# PS_TPS54340_Voltage_CurrentRev2.net
KiCad netlist of a schematic drawn in EAGLE
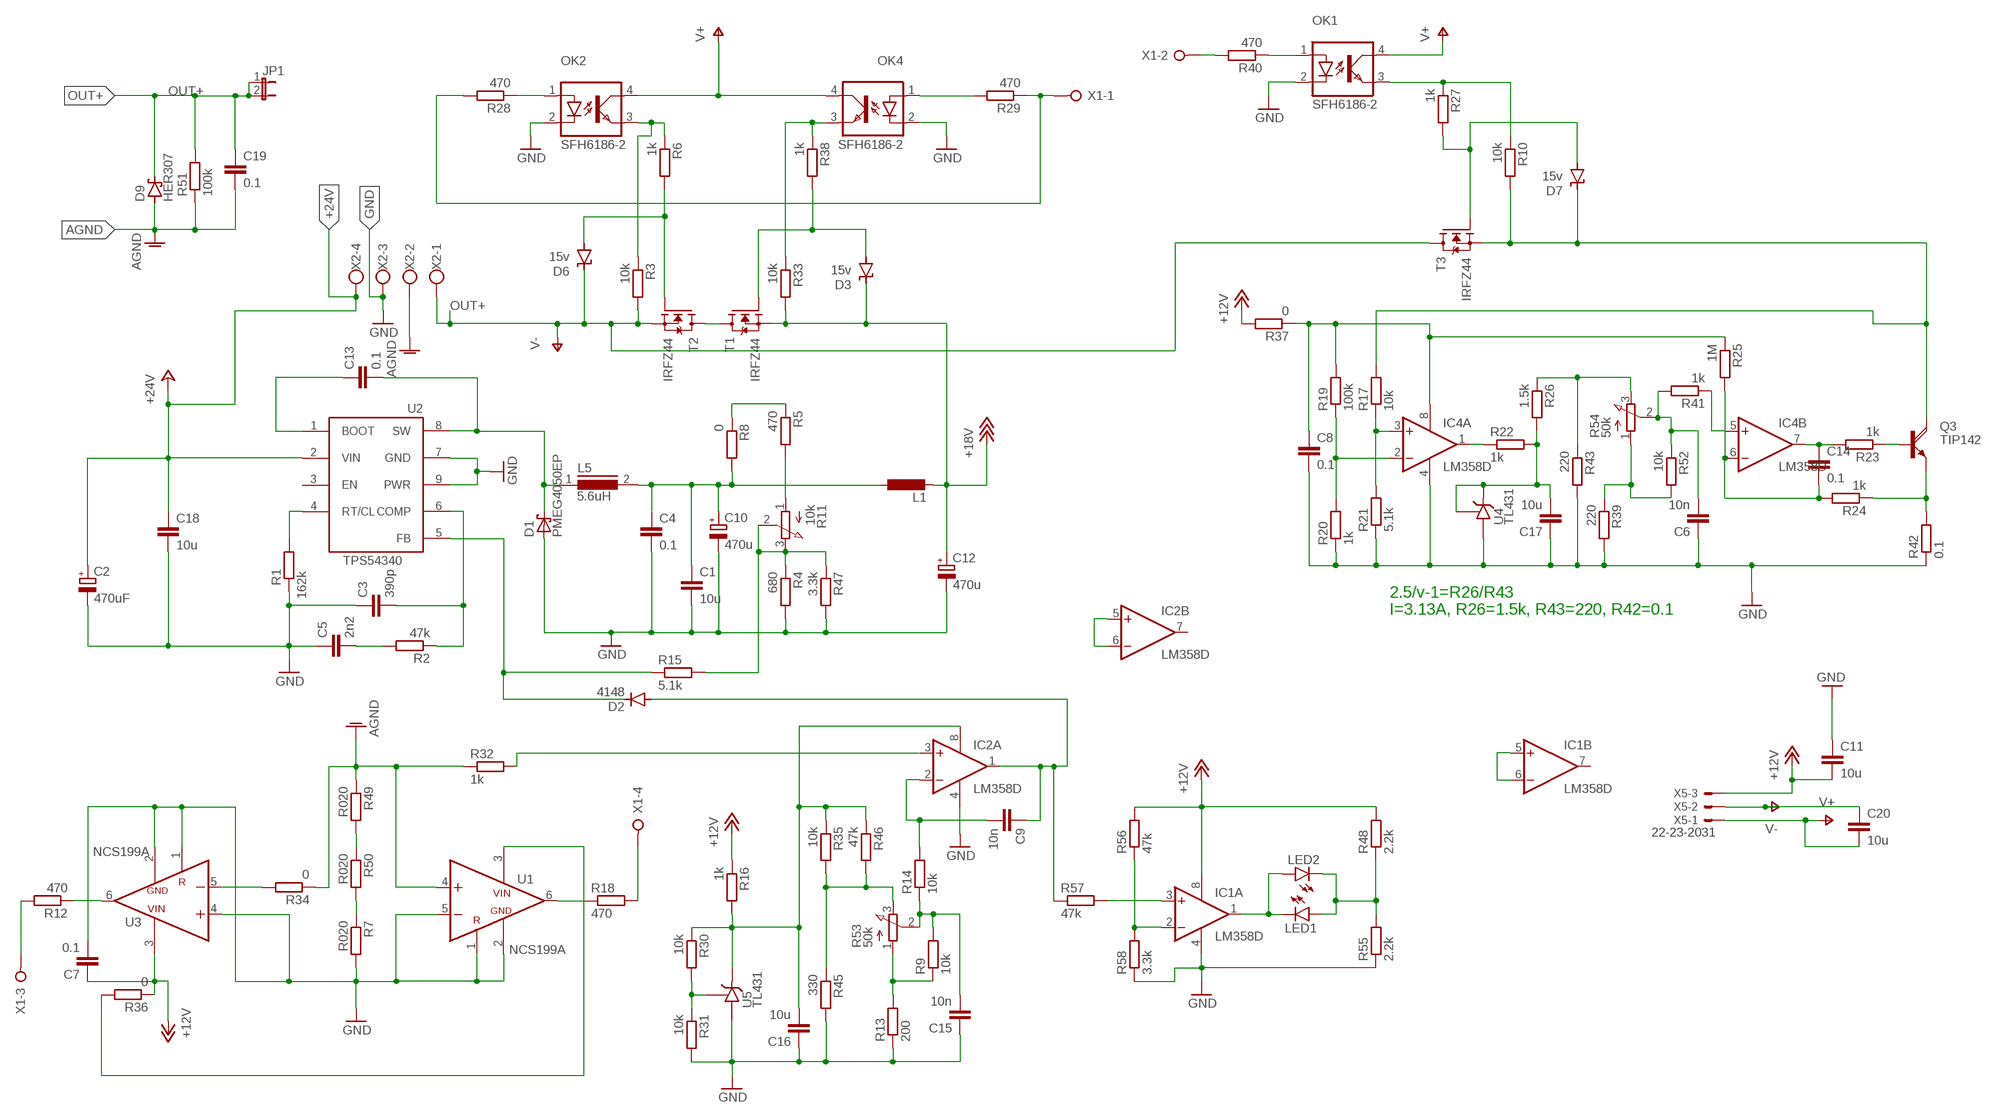
[diagram p0: schematic, sheet 1]

(export (version "E")
  (design (tool "Eeschema 10.0.6"))
  (components
    (comp (ref "C1")
      (value "10u")
      (footprint "eagle-import:C1210")
      (libsource (lib "eagle-import") (part "rcl_334_C-EUC1210"))
    )
    (comp (ref "C2")
      (value "470uF")
      (footprint "eagle-import:E5-10,5")
      (libsource (lib "eagle-import") (part "CPOL-EUE5-10.5"))
    )
    (comp (ref "C3")
      (value "390p")
      (footprint "eagle-import:C0603K")
      (libsource (lib "eagle-import") (part "rcl_334_C-EUC0603K"))
    )
    (comp (ref "C4")
      (value "0.1")
      (footprint "eagle-import:C1206")
      (libsource (lib "eagle-import") (part "C-EUC1206"))
    )
    (comp (ref "C5")
      (value "2n2")
      (footprint "eagle-import:C0603K")
      (libsource (lib "eagle-import") (part "rcl_334_C-EUC0603K"))
    )
    (comp (ref "C6")
      (value "10n")
      (footprint "eagle-import:C0603K")
      (libsource (lib "eagle-import") (part "rcl_334_C-EUC0603K"))
    )
    (comp (ref "C7")
      (value "0.1")
      (footprint "eagle-import:C0603K")
      (libsource (lib "eagle-import") (part "rcl_334_C-EUC0603K"))
    )
    (comp (ref "C8")
      (value "0.1")
      (footprint "eagle-import:C1206")
      (libsource (lib "eagle-import") (part "C-EUC1206"))
    )
    (comp (ref "C9")
      (value "10n")
      (footprint "eagle-import:C0603K")
      (libsource (lib "eagle-import") (part "rcl_334_C-EUC0603K"))
    )
    (comp (ref "C10")
      (value "470u")
      (footprint "eagle-import:E5-10,5")
      (libsource (lib "eagle-import") (part "CPOL-EUE5-10.5"))
    )
    (comp (ref "C11")
      (value "10u")
      (footprint "eagle-import:C1206")
      (libsource (lib "eagle-import") (part "C-EUC1206"))
    )
    (comp (ref "C12")
      (value "470u")
      (footprint "eagle-import:E5-10,5")
      (libsource (lib "eagle-import") (part "CPOL-EUE5-10.5"))
    )
    (comp (ref "C13")
      (value "0.1")
      (footprint "eagle-import:C102-043X133")
      (libsource (lib "eagle-import") (part "rcl_334_C-EU102-043X133"))
    )
    (comp (ref "C14")
      (value "0.1")
      (footprint "eagle-import:C1206")
      (libsource (lib "eagle-import") (part "C-EUC1206"))
    )
    (comp (ref "C15")
      (value "10n")
      (footprint "eagle-import:C0603K")
      (libsource (lib "eagle-import") (part "rcl_334_C-EUC0603K"))
    )
    (comp (ref "C16")
      (value "10u")
      (footprint "eagle-import:C0603K")
      (libsource (lib "eagle-import") (part "rcl_334_C-EUC0603K"))
    )
    (comp (ref "C17")
      (value "10u")
      (footprint "eagle-import:C0603K")
      (libsource (lib "eagle-import") (part "rcl_334_C-EUC0603K"))
    )
    (comp (ref "C18")
      (value "10u")
      (footprint "eagle-import:C1210")
      (libsource (lib "eagle-import") (part "rcl_334_C-EUC1210"))
    )
    (comp (ref "C19")
      (value "0.1")
      (footprint "eagle-import:C150-054X183")
      (libsource (lib "eagle-import") (part "rcl_334_C-EU150-054X183"))
    )
    (comp (ref "C20")
      (value "10u")
      (footprint "eagle-import:C1206")
      (libsource (lib "eagle-import") (part "C-EUC1206"))
    )
    (comp (ref "D1")
      (value "PMEG4050EP")
      (footprint "eagle-import:SOD128")
      (libsource (lib "eagle-import") (part "PMEG4050EP"))
    )
    (comp (ref "D2")
      (value "4148")
      (footprint "eagle-import:SOD80C")
      (libsource (lib "eagle-import") (part "PMLL41SOD80C"))
    )
    (comp (ref "D3")
      (value "15v")
      (footprint "eagle-import:SMBJ")
      (libsource (lib "eagle-import") (part "SUPPRESSOR-SMBJ"))
    )
    (comp (ref "D6")
      (value "15v")
      (footprint "eagle-import:SMBJ")
      (libsource (lib "eagle-import") (part "SUPPRESSOR-SMBJ"))
    )
    (comp (ref "D7")
      (value "15v")
      (footprint "eagle-import:SMBJ")
      (libsource (lib "eagle-import") (part "SUPPRESSOR-SMBJ"))
    )
    (comp (ref "D9")
      (value "HER307")
      (footprint "eagle-import:CB429-17")
      (libsource (lib "eagle-import") (part "15KEXX"))
    )
    (comp (ref "IC1")
      (value "LM358D")
      (footprint "eagle-import:SO08")
      (libsource (lib "eagle-import") (part "LM358D"))
    )
    (comp (ref "IC2")
      (value "LM358D")
      (footprint "eagle-import:SO08")
      (libsource (lib "eagle-import") (part "LM358D"))
    )
    (comp (ref "IC4")
      (value "LM358D")
      (footprint "eagle-import:SO08")
      (libsource (lib "eagle-import") (part "LM358D"))
    )
    (comp (ref "JP1")
      (value "JP1E")
      (footprint "eagle-import:JP1")
      (libsource (lib "eagle-import") (part "JP1E"))
    )
    (comp (ref "L1")
      (value "L-EU0207/5V")
      (footprint "eagle-import:0207_5V")
      (libsource (lib "eagle-import") (part "L-EU0207/5V"))
    )
    (comp (ref "L5")
      (value "5.6uH")
      (footprint "eagle-import:DR125")
      (libsource (lib "eagle-import") (part "DR125"))
    )
    (comp (ref "LED1")
      (value "LEDB152")
      (footprint "eagle-import:Q62902-B152")
      (libsource (lib "eagle-import") (part "LEDB152"))
    )
    (comp (ref "LED2")
      (value "LEDB152")
      (footprint "eagle-import:Q62902-B152")
      (libsource (lib "eagle-import") (part "LEDB152"))
    )
    (comp (ref "OK1")
      (value "SFH6186-2")
      (footprint "eagle-import:SMD4-7")
      (fields (field (name "MF") "VISHAY/TELEFUNKEN"))
      (libsource (lib "eagle-import") (part "SFH618?6-2"))
    )
    (comp (ref "OK2")
      (value "SFH6186-2")
      (footprint "eagle-import:SMD4-7")
      (fields (field (name "MF") "VISHAY/TELEFUNKEN"))
      (libsource (lib "eagle-import") (part "SFH618?6-2"))
    )
    (comp (ref "OK4")
      (value "SFH6186-2")
      (footprint "eagle-import:SMD4-7")
      (fields (field (name "MF") "VISHAY/TELEFUNKEN"))
      (libsource (lib "eagle-import") (part "SFH618?6-2"))
    )
    (comp (ref "Q3")
      (value "TIP142")
      (footprint "eagle-import:SOT93")
      (libsource (lib "eagle-import") (part "TIP142"))
    )
    (comp (ref "R1")
      (value "162k")
      (footprint "eagle-import:R1206")
      (libsource (lib "eagle-import") (part "R-EU_R1206"))
    )
    (comp (ref "R2")
      (value "47k")
      (footprint "eagle-import:R0603")
      (libsource (lib "eagle-import") (part "rcl_334_R-EU_R0603"))
    )
    (comp (ref "R3")
      (value "10k")
      (footprint "eagle-import:R0603")
      (libsource (lib "eagle-import") (part "rcl_334_R-EU_R0603"))
    )
    (comp (ref "R4")
      (value "680")
      (footprint "eagle-import:R1206")
      (libsource (lib "eagle-import") (part "R-EU_R1206"))
    )
    (comp (ref "R5")
      (value "470")
      (footprint "eagle-import:R1206")
      (libsource (lib "eagle-import") (part "R-EU_R1206"))
    )
    (comp (ref "R6")
      (value "1k")
      (footprint "eagle-import:R0603")
      (libsource (lib "eagle-import") (part "rcl_334_R-EU_R0603"))
    )
    (comp (ref "R7")
      (value "R020")
      (footprint "eagle-import:R1206")
      (libsource (lib "eagle-import") (part "R-EU_R1206"))
    )
    (comp (ref "R8")
      (value "0")
      (footprint "eagle-import:R0603")
      (libsource (lib "eagle-import") (part "rcl_334_R-EU_R0603"))
    )
    (comp (ref "R9")
      (value "10k")
      (footprint "eagle-import:R0603")
      (libsource (lib "eagle-import") (part "rcl_334_R-EU_R0603"))
    )
    (comp (ref "R10")
      (value "10k")
      (footprint "eagle-import:R0603")
      (libsource (lib "eagle-import") (part "rcl_334_R-EU_R0603"))
    )
    (comp (ref "R11")
      (value "10k")
      (footprint "eagle-import:3RP_1610N")
      (libsource (lib "eagle-import") (part "3RP/1610N"))
    )
    (comp (ref "R12")
      (value "470")
      (footprint "eagle-import:R0603")
      (libsource (lib "eagle-import") (part "rcl_334_R-EU_R0603"))
    )
    (comp (ref "R13")
      (value "200")
      (footprint "eagle-import:R0603")
      (libsource (lib "eagle-import") (part "rcl_334_R-EU_R0603"))
    )
    (comp (ref "R14")
      (value "10k")
      (footprint "eagle-import:R1206")
      (libsource (lib "eagle-import") (part "R-EU_R1206"))
    )
    (comp (ref "R15")
      (value "5.1k")
      (footprint "eagle-import:R0603")
      (libsource (lib "eagle-import") (part "rcl_334_R-EU_R0603"))
    )
    (comp (ref "R16")
      (value "1k")
      (footprint "eagle-import:R0603")
      (libsource (lib "eagle-import") (part "rcl_334_R-EU_R0603"))
    )
    (comp (ref "R17")
      (value "10k")
      (footprint "eagle-import:R1206")
      (libsource (lib "eagle-import") (part "R-EU_R1206"))
    )
    (comp (ref "R18")
      (value "470")
      (footprint "eagle-import:R0603")
      (libsource (lib "eagle-import") (part "rcl_334_R-EU_R0603"))
    )
    (comp (ref "R19")
      (value "100k")
      (footprint "eagle-import:R1206")
      (libsource (lib "eagle-import") (part "R-EU_R1206"))
    )
    (comp (ref "R20")
      (value "1k")
      (footprint "eagle-import:R1206")
      (libsource (lib "eagle-import") (part "R-EU_R1206"))
    )
    (comp (ref "R21")
      (value "5.1k")
      (footprint "eagle-import:R1206")
      (libsource (lib "eagle-import") (part "R-EU_R1206"))
    )
    (comp (ref "R22")
      (value "1k")
      (footprint "eagle-import:R0603")
      (libsource (lib "eagle-import") (part "rcl_334_R-EU_R0603"))
    )
    (comp (ref "R23")
      (value "1k")
      (footprint "eagle-import:R1206")
      (libsource (lib "eagle-import") (part "R-EU_R1206"))
    )
    (comp (ref "R24")
      (value "1k")
      (footprint "eagle-import:R1206")
      (libsource (lib "eagle-import") (part "R-EU_R1206"))
    )
    (comp (ref "R25")
      (value "1M")
      (footprint "eagle-import:R1206")
      (libsource (lib "eagle-import") (part "R-EU_R1206"))
    )
    (comp (ref "R26")
      (value "1.5k")
      (footprint "eagle-import:R0603")
      (libsource (lib "eagle-import") (part "rcl_334_R-EU_R0603"))
    )
    (comp (ref "R27")
      (value "1k")
      (footprint "eagle-import:R0603")
      (libsource (lib "eagle-import") (part "rcl_334_R-EU_R0603"))
    )
    (comp (ref "R28")
      (value "470")
      (footprint "eagle-import:R0603")
      (libsource (lib "eagle-import") (part "rcl_334_R-EU_R0603"))
    )
    (comp (ref "R29")
      (value "470")
      (footprint "eagle-import:R0603")
      (libsource (lib "eagle-import") (part "rcl_334_R-EU_R0603"))
    )
    (comp (ref "R30")
      (value "10k")
      (footprint "eagle-import:R0603")
      (libsource (lib "eagle-import") (part "rcl_334_R-EU_R0603"))
    )
    (comp (ref "R31")
      (value "10k")
      (footprint "eagle-import:R0603")
      (libsource (lib "eagle-import") (part "rcl_334_R-EU_R0603"))
    )
    (comp (ref "R32")
      (value "1k")
      (footprint "eagle-import:R1206")
      (libsource (lib "eagle-import") (part "R-EU_R1206"))
    )
    (comp (ref "R33")
      (value "10k")
      (footprint "eagle-import:R0603")
      (libsource (lib "eagle-import") (part "rcl_334_R-EU_R0603"))
    )
    (comp (ref "R34")
      (value "0")
      (footprint "eagle-import:R1206")
      (libsource (lib "eagle-import") (part "R-EU_R1206"))
    )
    (comp (ref "R35")
      (value "10k")
      (footprint "eagle-import:R0603")
      (libsource (lib "eagle-import") (part "rcl_334_R-EU_R0603"))
    )
    (comp (ref "R36")
      (value "0")
      (footprint "eagle-import:R1206")
      (libsource (lib "eagle-import") (part "R-EU_R1206"))
    )
    (comp (ref "R37")
      (value "0")
      (footprint "eagle-import:R1206")
      (libsource (lib "eagle-import") (part "R-EU_R1206"))
    )
    (comp (ref "R38")
      (value "1k")
      (footprint "eagle-import:R0603")
      (libsource (lib "eagle-import") (part "rcl_334_R-EU_R0603"))
    )
    (comp (ref "R39")
      (value "220")
      (footprint "eagle-import:R0603")
      (libsource (lib "eagle-import") (part "rcl_334_R-EU_R0603"))
    )
    (comp (ref "R40")
      (value "470")
      (footprint "eagle-import:R0603")
      (libsource (lib "eagle-import") (part "rcl_334_R-EU_R0603"))
    )
    (comp (ref "R41")
      (value "1k")
      (footprint "eagle-import:R1206")
      (libsource (lib "eagle-import") (part "R-EU_R1206"))
    )
    (comp (ref "R42")
      (value "0.1")
      (footprint "eagle-import:0414_15")
      (libsource (lib "eagle-import") (part "rcl_334_R-EU_0414/15"))
    )
    (comp (ref "R43")
      (value "220")
      (footprint "eagle-import:R0603")
      (libsource (lib "eagle-import") (part "rcl_334_R-EU_R0603"))
    )
    (comp (ref "R45")
      (value "330")
      (footprint "eagle-import:R0603")
      (libsource (lib "eagle-import") (part "rcl_334_R-EU_R0603"))
    )
    (comp (ref "R46")
      (value "47k")
      (footprint "eagle-import:R0603")
      (libsource (lib "eagle-import") (part "rcl_334_R-EU_R0603"))
    )
    (comp (ref "R47")
      (value "3.3k")
      (footprint "eagle-import:R1206")
      (libsource (lib "eagle-import") (part "R-EU_R1206"))
    )
    (comp (ref "R48")
      (value "2.2k")
      (footprint "eagle-import:R0603")
      (libsource (lib "eagle-import") (part "rcl_334_R-EU_R0603"))
    )
    (comp (ref "R49")
      (value "R020")
      (footprint "eagle-import:R1206")
      (libsource (lib "eagle-import") (part "R-EU_R1206"))
    )
    (comp (ref "R50")
      (value "R020")
      (footprint "eagle-import:R1206")
      (libsource (lib "eagle-import") (part "R-EU_R1206"))
    )
    (comp (ref "R51")
      (value "100k")
      (footprint "eagle-import:0207_15")
      (libsource (lib "eagle-import") (part "rcl_334_R-EU_0207/15"))
    )
    (comp (ref "R52")
      (value "10k")
      (footprint "eagle-import:R0603")
      (libsource (lib "eagle-import") (part "rcl_334_R-EU_R0603"))
    )
    (comp (ref "R53")
      (value "50k")
      (footprint "eagle-import:3RP_1610N")
      (libsource (lib "eagle-import") (part "3RP/1610N"))
    )
    (comp (ref "R54")
      (value "50k")
      (footprint "eagle-import:3RP_1610N")
      (libsource (lib "eagle-import") (part "3RP/1610N"))
    )
    (comp (ref "R55")
      (value "2.2k")
      (footprint "eagle-import:R0603")
      (libsource (lib "eagle-import") (part "rcl_334_R-EU_R0603"))
    )
    (comp (ref "R56")
      (value "47k")
      (footprint "eagle-import:R0603")
      (libsource (lib "eagle-import") (part "rcl_334_R-EU_R0603"))
    )
    (comp (ref "R57")
      (value "47k")
      (footprint "eagle-import:R0603")
      (libsource (lib "eagle-import") (part "rcl_334_R-EU_R0603"))
    )
    (comp (ref "R58")
      (value "3.3k")
      (footprint "eagle-import:R0603")
      (libsource (lib "eagle-import") (part "rcl_334_R-EU_R0603"))
    )
    (comp (ref "T1")
      (value "IRFZ44")
      (footprint "eagle-import:DPAK_TO252")
      (libsource (lib "eagle-import") (part "MOSFET-N-DPAK"))
    )
    (comp (ref "T2")
      (value "IRFZ44")
      (footprint "eagle-import:DPAK_TO252")
      (libsource (lib "eagle-import") (part "MOSFET-N-DPAK"))
    )
    (comp (ref "T3")
      (value "IRFZ44")
      (footprint "eagle-import:DPAK_TO252")
      (libsource (lib "eagle-import") (part "MOSFET-N-DPAK"))
    )
    (comp (ref "U1")
      (value "NCS199A")
      (footprint "eagle-import:SOT363")
      (libsource (lib "eagle-import") (part "NCS199A"))
    )
    (comp (ref "U2")
      (value "TPS54340")
      (footprint "eagle-import:HSOP")
      (libsource (lib "eagle-import") (part "TPS54340SO8"))
    )
    (comp (ref "U3")
      (value "NCS199A")
      (footprint "eagle-import:SOT363")
      (libsource (lib "eagle-import") (part "NCS199A"))
    )
    (comp (ref "U4")
      (value "TL431")
      (footprint "eagle-import:SOT23")
      (libsource (lib "eagle-import") (part "TL431"))
    )
    (comp (ref "U5")
      (value "TL431")
      (footprint "eagle-import:SOT23")
      (libsource (lib "eagle-import") (part "TL431"))
    )
    (comp (ref "X1")
      (value "W237-04P")
      (footprint "eagle-import:W237-4P")
      (libsource (lib "eagle-import") (part "W237-04P"))
    )
    (comp (ref "X2")
      (value "W237-4")
      (footprint "eagle-import:W237-4")
      (libsource (lib "eagle-import") (part "W237-4"))
    )
    (comp (ref "X5")
      (value "22-23-2031")
      (footprint "eagle-import:22-23-2031")
      (fields (field (name "MF") "MOLEX"))
      (libsource (lib "eagle-import") (part "22-23-2031"))
    )
  )
  (nets
    (net (code "1") (name "+12V") (class "Default")
      (node (ref "C11") (pin "2") (pinfunction "2_2") (pintype "passive"))
      (node (ref "C7") (pin "1") (pinfunction "1_1") (pintype "passive"))
      (node (ref "IC1") (pin "8") (pinfunction "V+_8") (pintype "power_in"))
      (node (ref "R16") (pin "1") (pinfunction "1_1") (pintype "passive"))
      (node (ref "R36") (pin "1") (pinfunction "1_1") (pintype "passive"))
      (node (ref "R37") (pin "2") (pinfunction "2_2") (pintype "passive"))
      (node (ref "R48") (pin "2") (pinfunction "2_2") (pintype "passive"))
      (node (ref "R56") (pin "2") (pinfunction "2_2") (pintype "passive"))
      (node (ref "U3") (pin "3") (pinfunction "VCC_3") (pintype "power_in"))
      (node (ref "X5") (pin "3") (pinfunction "S_3") (pintype "passive"))
    )
    (net (code "2") (name "+18V") (class "Default")
      (node (ref "C12") (pin "+") (pinfunction "+_+") (pintype "passive"))
      (node (ref "D3") (pin "C") (pinfunction "C_C") (pintype "passive"))
      (node (ref "L1") (pin "2") (pinfunction "2_2") (pintype "passive"))
      (node (ref "R33") (pin "2") (pinfunction "2_2") (pintype "passive"))
      (node (ref "T1") (pin "3") (pinfunction "S_3") (pintype "passive"))
    )
    (net (code "3") (name "+24V") (class "Default")
      (node (ref "C18") (pin "1") (pinfunction "1_1") (pintype "passive"))
      (node (ref "C2") (pin "+") (pinfunction "+_+") (pintype "passive"))
      (node (ref "U2") (pin "2") (pinfunction "VIN_2") (pintype "power_in"))
      (node (ref "X2") (pin "4") (pinfunction "KL_4") (pintype "passive"))
    )
    (net (code "4") (name "AGND") (class "Default")
      (node (ref "C19") (pin "2") (pinfunction "2_2") (pintype "passive"))
      (node (ref "D9") (pin "A") (pinfunction "A_A") (pintype "passive"))
      (node (ref "R32") (pin "1") (pinfunction "1_1") (pintype "passive"))
      (node (ref "R34") (pin "1") (pinfunction "1_1") (pintype "passive"))
      (node (ref "R49") (pin "1") (pinfunction "1_1") (pintype "passive"))
      (node (ref "R51") (pin "1") (pinfunction "1_1") (pintype "passive"))
      (node (ref "U1") (pin "4") (pinfunction "IN+_4") (pintype "input"))
      (node (ref "X2") (pin "2") (pinfunction "KL_2") (pintype "passive"))
    )
    (net (code "5") (name "GND") (class "Default")
      (node (ref "C1") (pin "2") (pinfunction "2_2") (pintype "passive"))
      (node (ref "C10") (pin "-") (pinfunction "-_-") (pintype "passive"))
      (node (ref "C11") (pin "1") (pinfunction "1_1") (pintype "passive"))
      (node (ref "C12") (pin "-") (pinfunction "-_-") (pintype "passive"))
      (node (ref "C15") (pin "1") (pinfunction "1_1") (pintype "passive"))
      (node (ref "C16") (pin "1") (pinfunction "1_1") (pintype "passive"))
      (node (ref "C17") (pin "1") (pinfunction "1_1") (pintype "passive"))
      (node (ref "C18") (pin "2") (pinfunction "2_2") (pintype "passive"))
      (node (ref "C2") (pin "-") (pinfunction "-_-") (pintype "passive"))
      (node (ref "C3") (pin "1") (pinfunction "1_1") (pintype "passive"))
      (node (ref "C4") (pin "2") (pinfunction "2_2") (pintype "passive"))
      (node (ref "C5") (pin "1") (pinfunction "1_1") (pintype "passive"))
      (node (ref "C6") (pin "1") (pinfunction "1_1") (pintype "passive"))
      (node (ref "C7") (pin "2") (pinfunction "2_2") (pintype "passive"))
      (node (ref "C8") (pin "2") (pinfunction "2_2") (pintype "passive"))
      (node (ref "D1") (pin "2") (pinfunction "A_2") (pintype "passive"))
      (node (ref "IC1") (pin "4") (pinfunction "V-_4") (pintype "power_in"))
      (node (ref "IC2") (pin "4") (pinfunction "V-_4") (pintype "power_in"))
      (node (ref "IC4") (pin "4") (pinfunction "V-_4") (pintype "power_in"))
      (node (ref "OK1") (pin "2") (pinfunction "C_2") (pintype "passive"))
      (node (ref "OK2") (pin "2") (pinfunction "C_2") (pintype "passive"))
      (node (ref "OK4") (pin "2") (pinfunction "C_2") (pintype "passive"))
      (node (ref "R1") (pin "1") (pinfunction "1_1") (pintype "passive"))
      (node (ref "R13") (pin "1") (pinfunction "1_1") (pintype "passive"))
      (node (ref "R20") (pin "1") (pinfunction "1_1") (pintype "passive"))
      (node (ref "R21") (pin "1") (pinfunction "1_1") (pintype "passive"))
      (node (ref "R31") (pin "2") (pinfunction "2_2") (pintype "passive"))
      (node (ref "R39") (pin "2") (pinfunction "2_2") (pintype "passive"))
      (node (ref "R4") (pin "2") (pinfunction "2_2") (pintype "passive"))
      (node (ref "R42") (pin "1") (pinfunction "1_1") (pintype "passive"))
      (node (ref "R43") (pin "2") (pinfunction "2_2") (pintype "passive"))
      (node (ref "R45") (pin "2") (pinfunction "2_2") (pintype "passive"))
      (node (ref "R47") (pin "2") (pinfunction "2_2") (pintype "passive"))
      (node (ref "R55") (pin "1") (pinfunction "1_1") (pintype "passive"))
      (node (ref "R58") (pin "1") (pinfunction "1_1") (pintype "passive"))
      (node (ref "R7") (pin "2") (pinfunction "2_2") (pintype "passive"))
      (node (ref "U1") (pin "1") (pinfunction "REF_1") (pintype "input"))
      (node (ref "U1") (pin "2") (pinfunction "GND_2") (pintype "power_in"))
      (node (ref "U1") (pin "5") (pinfunction "IN-_5") (pintype "input"))
      (node (ref "U2") (pin "7") (pinfunction "GND_7") (pintype "power_in"))
      (node (ref "U2") (pin "9") (pinfunction "PWR_9") (pintype "power_in"))
      (node (ref "U3") (pin "1") (pinfunction "REF_1") (pintype "input"))
      (node (ref "U3") (pin "2") (pinfunction "GND_2") (pintype "power_in"))
      (node (ref "U3") (pin "4") (pinfunction "IN+_4") (pintype "input"))
      (node (ref "U4") (pin "3") (pinfunction "A_3") (pintype "passive"))
      (node (ref "U5") (pin "3") (pinfunction "A_3") (pintype "passive"))
      (node (ref "X2") (pin "3") (pinfunction "KL_3") (pintype "passive"))
    )
    (net (code "6") (name "Net-(C1-Pad1)") (class "Default")
      (node (ref "C1") (pin "1") (pinfunction "1_1") (pintype "passive"))
      (node (ref "C10") (pin "+") (pinfunction "+_+") (pintype "passive"))
      (node (ref "C4") (pin "1") (pinfunction "1_1") (pintype "passive"))
      (node (ref "L1") (pin "1") (pinfunction "1_1") (pintype "passive"))
      (node (ref "L5") (pin "2") (pinfunction "2_2") (pintype "passive"))
      (node (ref "R8") (pin "2") (pinfunction "2_2") (pintype "passive"))
    )
    (net (code "7") (name "Net-(C5-Pad2)") (class "Default")
      (node (ref "C5") (pin "2") (pinfunction "2_2") (pintype "passive"))
      (node (ref "R2") (pin "2") (pinfunction "2_2") (pintype "passive"))
    )
    (net (code "8") (name "Net-(D1-K)") (class "Default")
      (node (ref "C13") (pin "2") (pinfunction "2_2") (pintype "passive"))
      (node (ref "D1") (pin "1") (pinfunction "K_1") (pintype "passive"))
      (node (ref "L5") (pin "1") (pinfunction "1_1") (pintype "passive"))
      (node (ref "U2") (pin "8") (pinfunction "SW_8") (pintype "power_in"))
    )
    (net (code "9") (name "Net-(IC1A-+IN)") (class "Default")
      (node (ref "IC1") (pin "3") (pinfunction "+IN_3") (pintype "input"))
      (node (ref "R57") (pin "2") (pinfunction "2_2") (pintype "passive"))
    )
    (net (code "10") (name "Net-(IC1A--IN)") (class "Default")
      (node (ref "IC1") (pin "2") (pinfunction "-IN_2") (pintype "input"))
      (node (ref "R56") (pin "1") (pinfunction "1_1") (pintype "passive"))
      (node (ref "R58") (pin "2") (pinfunction "2_2") (pintype "passive"))
    )
    (net (code "11") (name "Net-(IC1A-OUT)") (class "Default")
      (node (ref "IC1") (pin "1") (pinfunction "OUT_1") (pintype "output"))
      (node (ref "LED1") (pin "K") (pinfunction "C_K") (pintype "passive"))
      (node (ref "LED2") (pin "A") (pinfunction "A_A") (pintype "passive"))
    )
    (net (code "12") (name "Net-(IC1B-+IN)") (class "Default")
      (node (ref "IC1") (pin "5") (pinfunction "+IN_5") (pintype "input"))
      (node (ref "IC1") (pin "6") (pinfunction "-IN_6") (pintype "input"))
    )
    (net (code "13") (name "Net-(IC2A-+IN)") (class "Default")
      (node (ref "IC2") (pin "3") (pinfunction "+IN_3") (pintype "input"))
      (node (ref "R32") (pin "2") (pinfunction "2_2") (pintype "passive"))
    )
    (net (code "14") (name "Net-(IC2A--IN)") (class "Default")
      (node (ref "C9") (pin "2") (pinfunction "2_2") (pintype "passive"))
      (node (ref "IC2") (pin "2") (pinfunction "-IN_2") (pintype "input"))
      (node (ref "R14") (pin "2") (pinfunction "2_2") (pintype "passive"))
    )
    (net (code "15") (name "Net-(IC2A-OUT)") (class "Default")
      (node (ref "C9") (pin "1") (pinfunction "1_1") (pintype "passive"))
      (node (ref "D2") (pin "A") (pinfunction "A_A") (pintype "passive"))
      (node (ref "IC2") (pin "1") (pinfunction "OUT_1") (pintype "output"))
      (node (ref "R57") (pin "1") (pinfunction "1_1") (pintype "passive"))
    )
    (net (code "16") (name "Net-(IC2B-+IN)") (class "Default")
      (node (ref "IC2") (pin "5") (pinfunction "+IN_5") (pintype "input"))
      (node (ref "IC2") (pin "6") (pinfunction "-IN_6") (pintype "input"))
    )
    (net (code "17") (name "Net-(IC2C-V+)") (class "Default")
      (node (ref "C16") (pin "2") (pinfunction "2_2") (pintype "passive"))
      (node (ref "IC2") (pin "8") (pinfunction "V+_8") (pintype "power_in"))
      (node (ref "R16") (pin "2") (pinfunction "2_2") (pintype "passive"))
      (node (ref "R30") (pin "1") (pinfunction "1_1") (pintype "passive"))
      (node (ref "R35") (pin "1") (pinfunction "1_1") (pintype "passive"))
      (node (ref "R46") (pin "1") (pinfunction "1_1") (pintype "passive"))
      (node (ref "U5") (pin "1") (pinfunction "C_1") (pintype "passive"))
    )
    (net (code "18") (name "Net-(IC4A-+IN)") (class "Default")
      (node (ref "IC4") (pin "3") (pinfunction "+IN_3") (pintype "input"))
      (node (ref "R17") (pin "1") (pinfunction "1_1") (pintype "passive"))
      (node (ref "R21") (pin "2") (pinfunction "2_2") (pintype "passive"))
    )
    (net (code "19") (name "Net-(IC4A--IN)") (class "Default")
      (node (ref "IC4") (pin "2") (pinfunction "-IN_2") (pintype "input"))
      (node (ref "R19") (pin "1") (pinfunction "1_1") (pintype "passive"))
      (node (ref "R20") (pin "2") (pinfunction "2_2") (pintype "passive"))
    )
    (net (code "20") (name "Net-(IC4A-OUT)") (class "Default")
      (node (ref "IC4") (pin "1") (pinfunction "OUT_1") (pintype "output"))
      (node (ref "R22") (pin "1") (pinfunction "1_1") (pintype "passive"))
    )
    (net (code "21") (name "Net-(IC4B-+IN)") (class "Default")
      (node (ref "IC4") (pin "5") (pinfunction "+IN_5") (pintype "input"))
      (node (ref "R41") (pin "1") (pinfunction "1_1") (pintype "passive"))
    )
    (net (code "22") (name "Net-(IC4B--IN)") (class "Default")
      (node (ref "C14") (pin "2") (pinfunction "2_2") (pintype "passive"))
      (node (ref "IC4") (pin "6") (pinfunction "-IN_6") (pintype "input"))
      (node (ref "R24") (pin "2") (pinfunction "2_2") (pintype "passive"))
      (node (ref "R25") (pin "2") (pinfunction "2_2") (pintype "passive"))
    )
    (net (code "23") (name "Net-(IC4B-OUT)") (class "Default")
      (node (ref "C14") (pin "1") (pinfunction "1_1") (pintype "passive"))
      (node (ref "IC4") (pin "7") (pinfunction "OUT_7") (pintype "output"))
      (node (ref "R23") (pin "2") (pinfunction "2_2") (pintype "passive"))
    )
    (net (code "24") (name "Net-(IC4C-V+)") (class "Default")
      (node (ref "C8") (pin "1") (pinfunction "1_1") (pintype "passive"))
      (node (ref "IC4") (pin "8") (pinfunction "V+_8") (pintype "power_in"))
      (node (ref "R19") (pin "2") (pinfunction "2_2") (pintype "passive"))
      (node (ref "R25") (pin "1") (pinfunction "1_1") (pintype "passive"))
      (node (ref "R37") (pin "1") (pinfunction "1_1") (pintype "passive"))
    )
    (net (code "25") (name "Net-(LED2-C)") (class "Default")
      (node (ref "LED1") (pin "A") (pinfunction "A_A") (pintype "passive"))
      (node (ref "LED2") (pin "K") (pinfunction "C_K") (pintype "passive"))
      (node (ref "R48") (pin "1") (pinfunction "1_1") (pintype "passive"))
      (node (ref "R55") (pin "2") (pinfunction "2_2") (pintype "passive"))
    )
    (net (code "26") (name "Net-(OK1-A)") (class "Default")
      (node (ref "OK1") (pin "1") (pinfunction "A_1") (pintype "passive"))
      (node (ref "R40") (pin "1") (pinfunction "1_1") (pintype "passive"))
    )
    (net (code "27") (name "Net-(OK1-EMIT)") (class "Default")
      (node (ref "OK1") (pin "3") (pinfunction "EMIT_3") (pintype "passive"))
      (node (ref "R10") (pin "1") (pinfunction "1_1") (pintype "passive"))
      (node (ref "R27") (pin "1") (pinfunction "1_1") (pintype "passive"))
    )
    (net (code "28") (name "Net-(OK2-A)") (class "Default")
      (node (ref "OK2") (pin "1") (pinfunction "A_1") (pintype "passive"))
      (node (ref "R28") (pin "1") (pinfunction "1_1") (pintype "passive"))
    )
    (net (code "29") (name "Net-(OK2-EMIT)") (class "Default")
      (node (ref "OK2") (pin "3") (pinfunction "EMIT_3") (pintype "passive"))
      (node (ref "R3") (pin "1") (pinfunction "1_1") (pintype "passive"))
      (node (ref "R6") (pin "1") (pinfunction "1_1") (pintype "passive"))
    )
    (net (code "30") (name "Net-(OK4-A)") (class "Default")
      (node (ref "OK4") (pin "1") (pinfunction "A_1") (pintype "passive"))
      (node (ref "R29") (pin "2") (pinfunction "2_2") (pintype "passive"))
    )
    (net (code "31") (name "Net-(OK4-EMIT)") (class "Default")
      (node (ref "OK4") (pin "3") (pinfunction "EMIT_3") (pintype "passive"))
      (node (ref "R33") (pin "1") (pinfunction "1_1") (pintype "passive"))
      (node (ref "R38") (pin "1") (pinfunction "1_1") (pintype "passive"))
    )
    (net (code "32") (name "Net-(Q3-PadB)") (class "Default")
      (node (ref "Q3") (pin "B") (pinfunction "B_B") (pintype "passive"))
      (node (ref "R23") (pin "1") (pinfunction "1_1") (pintype "passive"))
    )
    (net (code "33") (name "Net-(Q3-PadE)") (class "Default")
      (node (ref "Q3") (pin "E") (pinfunction "E_E") (pintype "passive"))
      (node (ref "R24") (pin "1") (pinfunction "1_1") (pintype "passive"))
      (node (ref "R42") (pin "2") (pinfunction "2_2") (pintype "passive"))
    )
    (net (code "34") (name "Net-(R5-Pad1)") (class "Default")
      (node (ref "R5") (pin "1") (pinfunction "1_1") (pintype "passive"))
      (node (ref "R8") (pin "1") (pinfunction "1_1") (pintype "passive"))
    )
    (net (code "35") (name "Net-(R11-A)") (class "Default")
      (node (ref "R11") (pin "1") (pinfunction "A_1") (pintype "passive"))
      (node (ref "R5") (pin "2") (pinfunction "2_2") (pintype "passive"))
    )
    (net (code "36") (name "Net-(R11-E)") (class "Default")
      (node (ref "R11") (pin "2") (pinfunction "S_2") (pintype "passive"))
      (node (ref "R11") (pin "3") (pinfunction "E_3") (pintype "passive"))
      (node (ref "R15") (pin "2") (pinfunction "2_2") (pintype "passive"))
      (node (ref "R4") (pin "1") (pinfunction "1_1") (pintype "passive"))
      (node (ref "R47") (pin "1") (pinfunction "1_1") (pintype "passive"))
    )
    (net (code "37") (name "Net-(R49-Pad2)") (class "Default")
      (node (ref "R49") (pin "2") (pinfunction "2_2") (pintype "passive"))
      (node (ref "R50") (pin "1") (pinfunction "1_1") (pintype "passive"))
    )
    (net (code "38") (name "Net-(R50-Pad2)") (class "Default")
      (node (ref "R50") (pin "2") (pinfunction "2_2") (pintype "passive"))
      (node (ref "R7") (pin "1") (pinfunction "1_1") (pintype "passive"))
    )
    (net (code "39") (name "Net-(R53-A)") (class "Default")
      (node (ref "R13") (pin "2") (pinfunction "2_2") (pintype "passive"))
      (node (ref "R53") (pin "1") (pinfunction "A_1") (pintype "passive"))
      (node (ref "R9") (pin "1") (pinfunction "1_1") (pintype "passive"))
    )
    (net (code "40") (name "Net-(R53-E)") (class "Default")
      (node (ref "R35") (pin "2") (pinfunction "2_2") (pintype "passive"))
      (node (ref "R45") (pin "1") (pinfunction "1_1") (pintype "passive"))
      (node (ref "R46") (pin "2") (pinfunction "2_2") (pintype "passive"))
      (node (ref "R53") (pin "3") (pinfunction "E_3") (pintype "passive"))
    )
    (net (code "41") (name "Net-(R53-S)") (class "Default")
      (node (ref "C15") (pin "2") (pinfunction "2_2") (pintype "passive"))
      (node (ref "R14") (pin "1") (pinfunction "1_1") (pintype "passive"))
      (node (ref "R53") (pin "2") (pinfunction "S_2") (pintype "passive"))
      (node (ref "R9") (pin "2") (pinfunction "2_2") (pintype "passive"))
    )
    (net (code "42") (name "Net-(R54-A)") (class "Default")
      (node (ref "R39") (pin "1") (pinfunction "1_1") (pintype "passive"))
      (node (ref "R52") (pin "2") (pinfunction "2_2") (pintype "passive"))
      (node (ref "R54") (pin "1") (pinfunction "A_1") (pintype "passive"))
    )
    (net (code "43") (name "Net-(R54-E)") (class "Default")
      (node (ref "R26") (pin "1") (pinfunction "1_1") (pintype "passive"))
      (node (ref "R43") (pin "1") (pinfunction "1_1") (pintype "passive"))
      (node (ref "R54") (pin "3") (pinfunction "E_3") (pintype "passive"))
    )
    (net (code "44") (name "Net-(R54-S)") (class "Default")
      (node (ref "C6") (pin "2") (pinfunction "2_2") (pintype "passive"))
      (node (ref "R41") (pin "2") (pinfunction "2_2") (pintype "passive"))
      (node (ref "R52") (pin "1") (pinfunction "1_1") (pintype "passive"))
      (node (ref "R54") (pin "2") (pinfunction "S_2") (pintype "passive"))
    )
    (net (code "45") (name "Net-(T1-D)") (class "Default")
      (node (ref "T1") (pin "2") (pinfunction "D_2") (pintype "passive"))
      (node (ref "T2") (pin "2") (pinfunction "D_2") (pintype "passive"))
    )
    (net (code "46") (name "Net-(T1-G)") (class "Default")
      (node (ref "D3") (pin "A") (pinfunction "A_A") (pintype "passive"))
      (node (ref "R38") (pin "2") (pinfunction "2_2") (pintype "passive"))
      (node (ref "T1") (pin "1") (pinfunction "G_1") (pintype "passive"))
    )
    (net (code "47") (name "Net-(T2-G)") (class "Default")
      (node (ref "D6") (pin "A") (pinfunction "A_A") (pintype "passive"))
      (node (ref "R6") (pin "2") (pinfunction "2_2") (pintype "passive"))
      (node (ref "T2") (pin "1") (pinfunction "G_1") (pintype "passive"))
    )
    (net (code "48") (name "Net-(T3-G)") (class "Default")
      (node (ref "D7") (pin "A") (pinfunction "A_A") (pintype "passive"))
      (node (ref "R27") (pin "2") (pinfunction "2_2") (pintype "passive"))
      (node (ref "T3") (pin "1") (pinfunction "G_1") (pintype "passive"))
    )
    (net (code "49") (name "Net-(T3-S)") (class "Default")
      (node (ref "D7") (pin "C") (pinfunction "C_C") (pintype "passive"))
      (node (ref "Q3") (pin "C") (pinfunction "C_C") (pintype "passive"))
      (node (ref "R10") (pin "2") (pinfunction "2_2") (pintype "passive"))
      (node (ref "R17") (pin "2") (pinfunction "2_2") (pintype "passive"))
      (node (ref "T3") (pin "3") (pinfunction "S_3") (pintype "passive"))
    )
    (net (code "50") (name "Net-(U1-OUT)") (class "Default")
      (node (ref "R18") (pin "1") (pinfunction "1_1") (pintype "passive"))
      (node (ref "U1") (pin "6") (pinfunction "OUT_6") (pintype "output"))
    )
    (net (code "51") (name "Net-(U1-VCC)") (class "Default")
      (node (ref "R36") (pin "2") (pinfunction "2_2") (pintype "passive"))
      (node (ref "U1") (pin "3") (pinfunction "VCC_3") (pintype "power_in"))
    )
    (net (code "52") (name "Net-(U2-BOOT)") (class "Default")
      (node (ref "C13") (pin "1") (pinfunction "1_1") (pintype "passive"))
      (node (ref "U2") (pin "1") (pinfunction "BOOT_1") (pintype "input"))
    )
    (net (code "53") (name "Net-(U2-COMP)") (class "Default")
      (node (ref "C3") (pin "2") (pinfunction "2_2") (pintype "passive"))
      (node (ref "R2") (pin "1") (pinfunction "1_1") (pintype "passive"))
      (node (ref "U2") (pin "6") (pinfunction "COMP_6") (pintype "input"))
    )
    (net (code "54") (name "Net-(U2-FB)") (class "Default")
      (node (ref "D2") (pin "C") (pinfunction "C_C") (pintype "passive"))
      (node (ref "R15") (pin "1") (pinfunction "1_1") (pintype "passive"))
      (node (ref "U2") (pin "5") (pinfunction "FB_5") (pintype "input"))
    )
    (net (code "55") (name "Net-(U2-RT{slash}CL)") (class "Default")
      (node (ref "R1") (pin "2") (pinfunction "2_2") (pintype "passive"))
      (node (ref "U2") (pin "4") (pinfunction "RT/CL_4") (pintype "input"))
    )
    (net (code "56") (name "Net-(U3-IN-)") (class "Default")
      (node (ref "R34") (pin "2") (pinfunction "2_2") (pintype "passive"))
      (node (ref "U3") (pin "5") (pinfunction "IN-_5") (pintype "input"))
    )
    (net (code "57") (name "Net-(U3-OUT)") (class "Default")
      (node (ref "R12") (pin "1") (pinfunction "1_1") (pintype "passive"))
      (node (ref "U3") (pin "6") (pinfunction "OUT_6") (pintype "output"))
    )
    (net (code "58") (name "Net-(U4-C)") (class "Default")
      (node (ref "C17") (pin "2") (pinfunction "2_2") (pintype "passive"))
      (node (ref "R22") (pin "2") (pinfunction "2_2") (pintype "passive"))
      (node (ref "R26") (pin "2") (pinfunction "2_2") (pintype "passive"))
      (node (ref "U4") (pin "1") (pinfunction "C_1") (pintype "passive"))
      (node (ref "U4") (pin "2") (pinfunction "R_2") (pintype "passive"))
    )
    (net (code "59") (name "Net-(U5-R)") (class "Default")
      (node (ref "R30") (pin "2") (pinfunction "2_2") (pintype "passive"))
      (node (ref "R31") (pin "1") (pinfunction "1_1") (pintype "passive"))
      (node (ref "U5") (pin "2") (pinfunction "R_2") (pintype "passive"))
    )
    (net (code "60") (name "Net-(X1A-KL)") (class "Default")
      (node (ref "R28") (pin "2") (pinfunction "2_2") (pintype "passive"))
      (node (ref "R29") (pin "1") (pinfunction "1_1") (pintype "passive"))
      (node (ref "X1") (pin "1") (pinfunction "KL_1") (pintype "passive"))
    )
    (net (code "61") (name "Net-(X1B-KL)") (class "Default")
      (node (ref "R40") (pin "2") (pinfunction "2_2") (pintype "passive"))
      (node (ref "X1") (pin "2") (pinfunction "KL_2") (pintype "passive"))
    )
    (net (code "62") (name "Net-(X1C-KL)") (class "Default")
      (node (ref "R12") (pin "2") (pinfunction "2_2") (pintype "passive"))
      (node (ref "X1") (pin "3") (pinfunction "KL_3") (pintype "passive"))
    )
    (net (code "63") (name "Net-(X1D-KL)") (class "Default")
      (node (ref "R18") (pin "2") (pinfunction "2_2") (pintype "passive"))
      (node (ref "X1") (pin "4") (pinfunction "KL_4") (pintype "passive"))
    )
    (net (code "64") (name "OUT+") (class "Default")
      (node (ref "C19") (pin "1") (pinfunction "1_1") (pintype "passive"))
      (node (ref "C20") (pin "1") (pinfunction "1_1") (pintype "passive"))
      (node (ref "D6") (pin "C") (pinfunction "C_C") (pintype "passive"))
      (node (ref "D9") (pin "C") (pinfunction "C_C") (pintype "passive"))
      (node (ref "JP1") (pin "1") (pinfunction "1_1") (pintype "passive"))
      (node (ref "JP1") (pin "2") (pinfunction "2_2") (pintype "passive"))
      (node (ref "R3") (pin "2") (pinfunction "2_2") (pintype "passive"))
      (node (ref "R51") (pin "2") (pinfunction "2_2") (pintype "passive"))
      (node (ref "T2") (pin "3") (pinfunction "S_3") (pintype "passive"))
      (node (ref "T3") (pin "2") (pinfunction "D_2") (pintype "passive"))
      (node (ref "X2") (pin "1") (pinfunction "KL_1") (pintype "passive"))
      (node (ref "X5") (pin "2") (pinfunction "S_2") (pintype "passive"))
    )
    (net (code "65") (name "V+") (class "Default")
      (node (ref "C20") (pin "2") (pinfunction "2_2") (pintype "passive"))
      (node (ref "OK1") (pin "4") (pinfunction "COL_4") (pintype "passive"))
      (node (ref "OK2") (pin "4") (pinfunction "COL_4") (pintype "passive"))
      (node (ref "OK4") (pin "4") (pinfunction "COL_4") (pintype "passive"))
      (node (ref "X5") (pin "1") (pinfunction "S_1") (pintype "passive"))
    )
    (net (code "66") (name "unconnected-(IC1B-OUT-Pad7)") (class "Default")
      (node (ref "IC1") (pin "7") (pinfunction "OUT_7") (pintype "output"))
    )
    (net (code "67") (name "unconnected-(IC2B-OUT-Pad7)") (class "Default")
      (node (ref "IC2") (pin "7") (pinfunction "OUT_7") (pintype "output"))
    )
    (net (code "68") (name "unconnected-(U2-EN-Pad3)") (class "Default")
      (node (ref "U2") (pin "3") (pinfunction "EN_3") (pintype "input"))
    )
  )
)
